# PulseGenerator.net
KiCad netlist of a schematic drawn in EAGLE
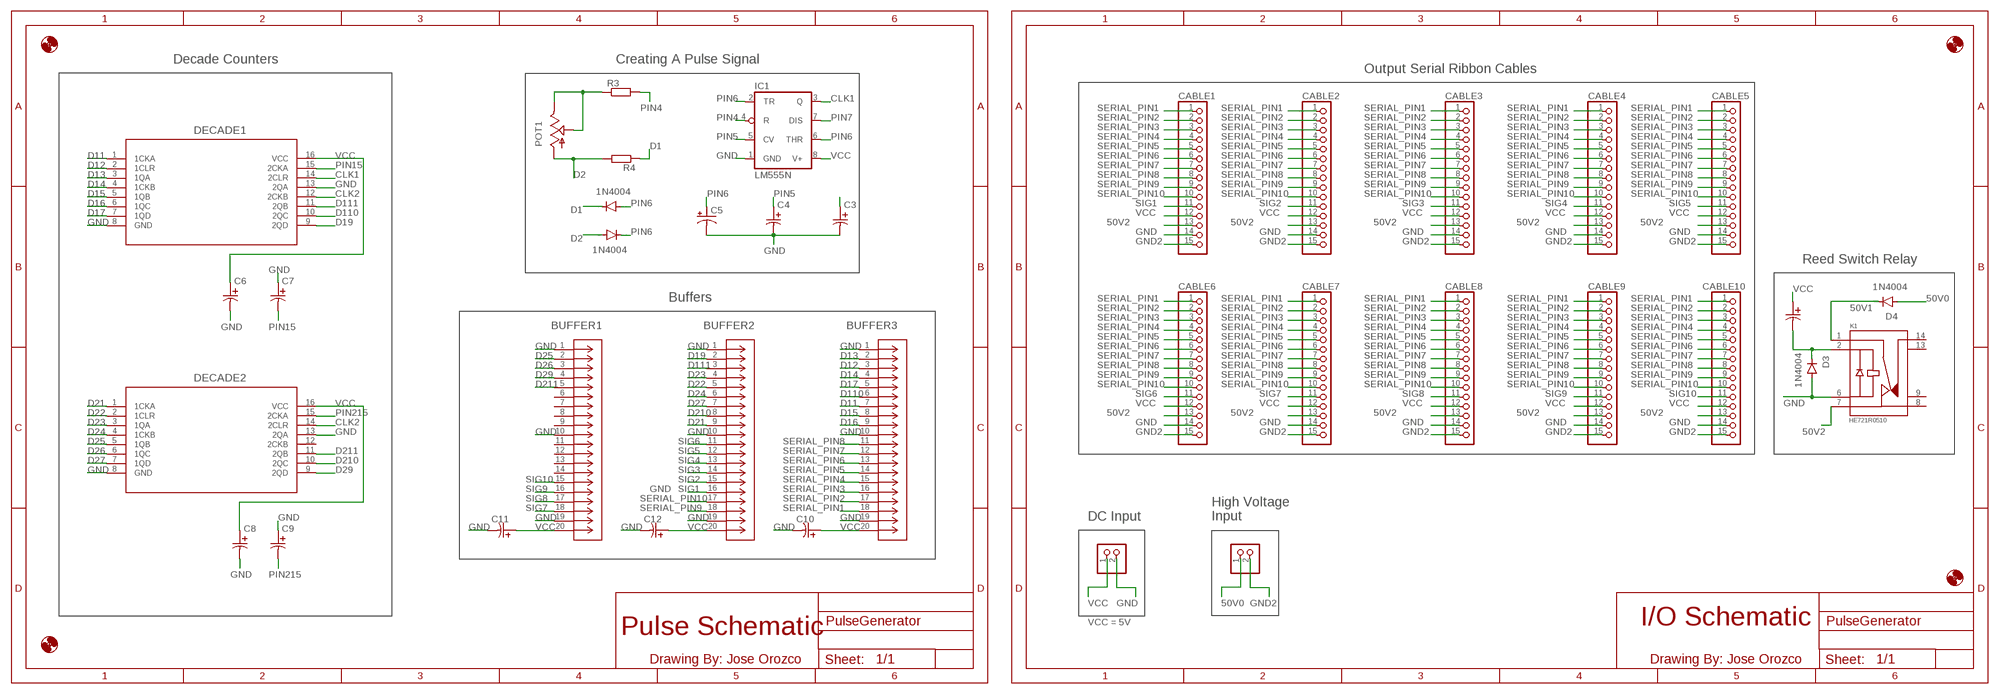
[diagram p0: schematic, sheet 1]

(export (version "E")
  (design (tool "Eeschema 10.0.6"))
  (components
    (comp (ref "BUFFER1")
      (value "4820-3000-CP")
      (footprint "eagle-import:CONN_3000_3MM")
      (fields (field (name "COPYRIGHT") "Copyright (C) 2018 Accelerated Designs. All rights reserved"))
      (libsource (lib "eagle-import") (part "4820-3000-CP"))
    )
    (comp (ref "BUFFER2")
      (value "4820-3000-CP")
      (footprint "eagle-import:CONN_3000_3MM")
      (fields (field (name "COPYRIGHT") "Copyright (C) 2018 Accelerated Designs. All rights reserved"))
      (libsource (lib "eagle-import") (part "4820-3000-CP"))
    )
    (comp (ref "BUFFER3")
      (value "4820-3000-CP")
      (footprint "eagle-import:CONN_3000_3MM")
      (fields (field (name "COPYRIGHT") "Copyright (C) 2018 Accelerated Designs. All rights reserved"))
      (libsource (lib "eagle-import") (part "4820-3000-CP"))
    )
    (comp (ref "C1")
      (value "C322C104K5R5TA")
      (footprint "eagle-import:CAP_C322_KEM")
      (libsource (lib "eagle-import") (part "C322C104K5R5TA"))
    )
    (comp (ref "C3")
      (value "C322C104K5R5TA")
      (footprint "eagle-import:CAP_C322_KEM")
      (libsource (lib "eagle-import") (part "C322C104K5R5TA"))
    )
    (comp (ref "C4")
      (value "C322C104K5R5TA")
      (footprint "eagle-import:CAP_C322_KEM")
      (libsource (lib "eagle-import") (part "C322C104K5R5TA"))
    )
    (comp (ref "C5")
      (value "CPOL-USTAP5-45")
      (footprint "eagle-import:TAP5-45")
      (libsource (lib "eagle-import") (part "CPOL-USTAP5-45"))
    )
    (comp (ref "C6")
      (value "C322C104K5R5TA")
      (footprint "eagle-import:CAP_C322_KEM")
      (libsource (lib "eagle-import") (part "C322C104K5R5TA"))
    )
    (comp (ref "C7")
      (value "C322C104K5R5TA")
      (footprint "eagle-import:CAP_C322_KEM")
      (libsource (lib "eagle-import") (part "C322C104K5R5TA"))
    )
    (comp (ref "C8")
      (value "C322C104K5R5TA")
      (footprint "eagle-import:CAP_C322_KEM")
      (libsource (lib "eagle-import") (part "C322C104K5R5TA"))
    )
    (comp (ref "C9")
      (value "C322C104K5R5TA")
      (footprint "eagle-import:CAP_C322_KEM")
      (libsource (lib "eagle-import") (part "C322C104K5R5TA"))
    )
    (comp (ref "C10")
      (value "C322C104K5R5TA")
      (footprint "eagle-import:CAP_C322_KEM")
      (libsource (lib "eagle-import") (part "C322C104K5R5TA"))
    )
    (comp (ref "C11")
      (value "C322C104K5R5TA")
      (footprint "eagle-import:CAP_C322_KEM")
      (libsource (lib "eagle-import") (part "C322C104K5R5TA"))
    )
    (comp (ref "C12")
      (value "C322C104K5R5TA")
      (footprint "eagle-import:CAP_C322_KEM")
      (libsource (lib "eagle-import") (part "C322C104K5R5TA"))
    )
    (comp (ref "CABLE1")
      (value "PINHD-1X15")
      (footprint "eagle-import:1X15")
      (libsource (lib "eagle-import") (part "PINHD-1X15"))
    )
    (comp (ref "CABLE2")
      (value "PINHD-1X15")
      (footprint "eagle-import:1X15")
      (libsource (lib "eagle-import") (part "PINHD-1X15"))
    )
    (comp (ref "CABLE3")
      (value "PINHD-1X15")
      (footprint "eagle-import:1X15")
      (libsource (lib "eagle-import") (part "PINHD-1X15"))
    )
    (comp (ref "CABLE4")
      (value "PINHD-1X15")
      (footprint "eagle-import:1X15")
      (libsource (lib "eagle-import") (part "PINHD-1X15"))
    )
    (comp (ref "CABLE5")
      (value "PINHD-1X15")
      (footprint "eagle-import:1X15")
      (libsource (lib "eagle-import") (part "PINHD-1X15"))
    )
    (comp (ref "CABLE6")
      (value "PINHD-1X15")
      (footprint "eagle-import:1X15")
      (libsource (lib "eagle-import") (part "PINHD-1X15"))
    )
    (comp (ref "CABLE7")
      (value "PINHD-1X15")
      (footprint "eagle-import:1X15")
      (libsource (lib "eagle-import") (part "PINHD-1X15"))
    )
    (comp (ref "CABLE8")
      (value "PINHD-1X15")
      (footprint "eagle-import:1X15")
      (libsource (lib "eagle-import") (part "PINHD-1X15"))
    )
    (comp (ref "CABLE9")
      (value "PINHD-1X15")
      (footprint "eagle-import:1X15")
      (libsource (lib "eagle-import") (part "PINHD-1X15"))
    )
    (comp (ref "CABLE10")
      (value "PINHD-1X15")
      (footprint "eagle-import:1X15")
      (libsource (lib "eagle-import") (part "PINHD-1X15"))
    )
    (comp (ref "D1")
      (value "1N4004")
      (footprint "eagle-import:DO41-10")
      (libsource (lib "eagle-import") (part "1N4004"))
    )
    (comp (ref "D2")
      (value "1N4004")
      (footprint "eagle-import:DO41-10")
      (libsource (lib "eagle-import") (part "1N4004"))
    )
    (comp (ref "D3")
      (value "1N4004")
      (footprint "eagle-import:DO41-10")
      (libsource (lib "eagle-import") (part "1N4004"))
    )
    (comp (ref "D4")
      (value "1N4004")
      (footprint "eagle-import:DO41-10")
      (libsource (lib "eagle-import") (part "1N4004"))
    )
    (comp (ref "DECADE1")
      (value "SN74LS390N")
      (footprint "eagle-import:N16")
      (fields
        (field (name "GENERIC_PART_NUMBER") "SN74LS390")
        (field (name "MANUFACTURER") "Texas Instruments")
      )
      (libsource (lib "eagle-import") (part "SN74LS390N"))
    )
    (comp (ref "DECADE2")
      (value "SN74LS390N")
      (footprint "eagle-import:N16")
      (fields
        (field (name "GENERIC_PART_NUMBER") "SN74LS390")
        (field (name "MANUFACTURER") "Texas Instruments")
      )
      (libsource (lib "eagle-import") (part "SN74LS390N"))
    )
    (comp (ref "H1")
      (value "MOUNT-HOLE2.8")
      (footprint "eagle-import:2,8")
      (libsource (lib "eagle-import") (part "MOUNT-HOLE2.8"))
    )
    (comp (ref "H2")
      (value "MOUNT-HOLE2.8")
      (footprint "eagle-import:2,8")
      (libsource (lib "eagle-import") (part "MOUNT-HOLE2.8"))
    )
    (comp (ref "H3")
      (value "MOUNT-HOLE2.8")
      (footprint "eagle-import:2,8")
      (libsource (lib "eagle-import") (part "MOUNT-HOLE2.8"))
    )
    (comp (ref "H4")
      (value "MOUNT-HOLE2.8")
      (footprint "eagle-import:2,8")
      (libsource (lib "eagle-import") (part "MOUNT-HOLE2.8"))
    )
    (comp (ref "IC1")
      (value "LM555N")
      (footprint "eagle-import:DIL08")
      (libsource (lib "eagle-import") (part "555NLM"))
    )
    (comp (ref "JP1")
      (value "PINHD-1X2")
      (footprint "eagle-import:1X02")
      (libsource (lib "eagle-import") (part "PINHD-1X2"))
    )
    (comp (ref "JP2")
      (value "PINHD-1X2")
      (footprint "eagle-import:1X02")
      (libsource (lib "eagle-import") (part "PINHD-1X2"))
    )
    (comp (ref "K1")
      (value "HE721R0510")
      (footprint "eagle-import:RELAY_HE721R0510")
      (fields (field (name "DIGI-KEY_PART_NUMBER") "F11467-ND") (field (name "MF") "Littelfuse Inc."))
      (libsource (lib "eagle-import") (part "HE721R0510"))
    )
    (comp (ref "POT1")
      (value "TRIM_US-S63X")
      (footprint "eagle-import:S63X")
      (libsource (lib "eagle-import") (part "TRIM_US-S63X"))
    )
    (comp (ref "R3")
      (value "R-EU_0309/10")
      (footprint "eagle-import:0309_10")
      (libsource (lib "eagle-import") (part "R-EU_0309/10"))
    )
    (comp (ref "R4")
      (value "R-EU_0309/10")
      (footprint "eagle-import:0309_10")
      (libsource (lib "eagle-import") (part "R-EU_0309/10"))
    )
  )
  (nets
    (net (code "1") (name "/50V0") (class "Default")
      (node (ref "D4") (pin "A") (pinfunction "A_A") (pintype "passive"))
      (node (ref "JP2") (pin "1") (pinfunction "1_1") (pintype "passive"))
    )
    (net (code "2") (name "/50V1") (class "Default")
      (node (ref "D4") (pin "C") (pinfunction "C_C") (pintype "passive"))
      (node (ref "K1") (pin "1") (pinfunction "1_1") (pintype "passive"))
    )
    (net (code "3") (name "/50V2") (class "Default")
      (node (ref "CABLE1") (pin "13") (pinfunction "13_13") (pintype "passive"))
      (node (ref "CABLE10") (pin "13") (pinfunction "13_13") (pintype "passive"))
      (node (ref "CABLE2") (pin "13") (pinfunction "13_13") (pintype "passive"))
      (node (ref "CABLE3") (pin "13") (pinfunction "13_13") (pintype "passive"))
      (node (ref "CABLE4") (pin "13") (pinfunction "13_13") (pintype "passive"))
      (node (ref "CABLE5") (pin "13") (pinfunction "13_13") (pintype "passive"))
      (node (ref "CABLE6") (pin "13") (pinfunction "13_13") (pintype "passive"))
      (node (ref "CABLE7") (pin "13") (pinfunction "13_13") (pintype "passive"))
      (node (ref "CABLE8") (pin "13") (pinfunction "13_13") (pintype "passive"))
      (node (ref "CABLE9") (pin "13") (pinfunction "13_13") (pintype "passive"))
      (node (ref "K1") (pin "7") (pinfunction "7_7") (pintype "passive"))
    )
    (net (code "4") (name "/CLK1") (class "Default")
      (node (ref "DECADE1") (pin "14") (pinfunction "2CLR_14") (pintype "input"))
      (node (ref "IC1") (pin "3") (pinfunction "Q_3") (pintype "output"))
    )
    (net (code "5") (name "/CLK2") (class "Default")
      (node (ref "DECADE1") (pin "12") (pinfunction "2CKB_12") (pintype "input"))
      (node (ref "DECADE2") (pin "14") (pinfunction "2CLR_14") (pintype "input"))
    )
    (net (code "6") (name "/D1") (class "Default")
      (node (ref "D1") (pin "C") (pinfunction "C_C") (pintype "passive"))
      (node (ref "R4") (pin "1") (pinfunction "1_1") (pintype "passive"))
    )
    (net (code "7") (name "/D2") (class "Default")
      (node (ref "D2") (pin "A") (pinfunction "A_A") (pintype "passive"))
      (node (ref "POT1") (pin "A") (pinfunction "A_A") (pintype "passive"))
      (node (ref "R4") (pin "2") (pinfunction "2_2") (pintype "passive"))
    )
    (net (code "8") (name "/D11") (class "Default")
      (node (ref "BUFFER3") (pin "7") (pinfunction "7_7") (pintype "passive"))
      (node (ref "DECADE1") (pin "1") (pinfunction "1CKA_1") (pintype "input"))
    )
    (net (code "9") (name "/D12") (class "Default")
      (node (ref "BUFFER3") (pin "3") (pinfunction "3_3") (pintype "passive"))
      (node (ref "DECADE1") (pin "2") (pinfunction "1CLR_2") (pintype "input"))
    )
    (net (code "10") (name "/D13") (class "Default")
      (node (ref "BUFFER3") (pin "2") (pinfunction "2_2") (pintype "passive"))
      (node (ref "DECADE1") (pin "3") (pinfunction "1QA_3") (pintype "output"))
    )
    (net (code "11") (name "/D14") (class "Default")
      (node (ref "BUFFER3") (pin "4") (pinfunction "4_4") (pintype "passive"))
      (node (ref "DECADE1") (pin "4") (pinfunction "1CKB_4") (pintype "input"))
    )
    (net (code "12") (name "/D15") (class "Default")
      (node (ref "BUFFER3") (pin "8") (pinfunction "8_8") (pintype "passive"))
      (node (ref "DECADE1") (pin "5") (pinfunction "1QB_5") (pintype "output"))
    )
    (net (code "13") (name "/D16") (class "Default")
      (node (ref "BUFFER3") (pin "9") (pinfunction "9_9") (pintype "passive"))
      (node (ref "DECADE1") (pin "6") (pinfunction "1QC_6") (pintype "output"))
    )
    (net (code "14") (name "/D17") (class "Default")
      (node (ref "BUFFER3") (pin "5") (pinfunction "5_5") (pintype "passive"))
      (node (ref "DECADE1") (pin "7") (pinfunction "1QD_7") (pintype "output"))
    )
    (net (code "15") (name "/D19") (class "Default")
      (node (ref "BUFFER2") (pin "2") (pinfunction "2_2") (pintype "passive"))
      (node (ref "DECADE1") (pin "9") (pinfunction "2QD_9") (pintype "output"))
    )
    (net (code "16") (name "/D21") (class "Default")
      (node (ref "BUFFER2") (pin "9") (pinfunction "9_9") (pintype "passive"))
      (node (ref "DECADE2") (pin "1") (pinfunction "1CKA_1") (pintype "input"))
    )
    (net (code "17") (name "/D22") (class "Default")
      (node (ref "BUFFER2") (pin "5") (pinfunction "5_5") (pintype "passive"))
      (node (ref "DECADE2") (pin "2") (pinfunction "1CLR_2") (pintype "input"))
    )
    (net (code "18") (name "/D23") (class "Default")
      (node (ref "BUFFER2") (pin "4") (pinfunction "4_4") (pintype "passive"))
      (node (ref "DECADE2") (pin "3") (pinfunction "1QA_3") (pintype "output"))
    )
    (net (code "19") (name "/D24") (class "Default")
      (node (ref "BUFFER2") (pin "6") (pinfunction "6_6") (pintype "passive"))
      (node (ref "DECADE2") (pin "4") (pinfunction "1CKB_4") (pintype "input"))
    )
    (net (code "20") (name "/D25") (class "Default")
      (node (ref "BUFFER1") (pin "2") (pinfunction "2_2") (pintype "passive"))
      (node (ref "DECADE2") (pin "5") (pinfunction "1QB_5") (pintype "output"))
    )
    (net (code "21") (name "/D26") (class "Default")
      (node (ref "BUFFER1") (pin "3") (pinfunction "3_3") (pintype "passive"))
      (node (ref "DECADE2") (pin "6") (pinfunction "1QC_6") (pintype "output"))
    )
    (net (code "22") (name "/D27") (class "Default")
      (node (ref "BUFFER2") (pin "7") (pinfunction "7_7") (pintype "passive"))
      (node (ref "DECADE2") (pin "7") (pinfunction "1QD_7") (pintype "output"))
    )
    (net (code "23") (name "/D29") (class "Default")
      (node (ref "BUFFER1") (pin "4") (pinfunction "4_4") (pintype "passive"))
      (node (ref "DECADE2") (pin "9") (pinfunction "2QD_9") (pintype "output"))
    )
    (net (code "24") (name "/D110") (class "Default")
      (node (ref "BUFFER3") (pin "6") (pinfunction "6_6") (pintype "passive"))
      (node (ref "DECADE1") (pin "10") (pinfunction "2QC_10") (pintype "output"))
    )
    (net (code "25") (name "/D111") (class "Default")
      (node (ref "BUFFER2") (pin "3") (pinfunction "3_3") (pintype "passive"))
      (node (ref "DECADE1") (pin "11") (pinfunction "2QB_11") (pintype "output"))
    )
    (net (code "26") (name "/D210") (class "Default")
      (node (ref "BUFFER2") (pin "8") (pinfunction "8_8") (pintype "passive"))
      (node (ref "DECADE2") (pin "10") (pinfunction "2QC_10") (pintype "output"))
    )
    (net (code "27") (name "/D211") (class "Default")
      (node (ref "BUFFER1") (pin "5") (pinfunction "5_5") (pintype "passive"))
      (node (ref "DECADE2") (pin "11") (pinfunction "2QB_11") (pintype "output"))
    )
    (net (code "28") (name "/GND") (class "Default")
      (node (ref "BUFFER1") (pin "1") (pinfunction "1_1") (pintype "passive"))
      (node (ref "BUFFER1") (pin "10") (pinfunction "10_10") (pintype "passive"))
      (node (ref "BUFFER1") (pin "19") (pinfunction "19_19") (pintype "passive"))
      (node (ref "BUFFER2") (pin "1") (pinfunction "1_1") (pintype "passive"))
      (node (ref "BUFFER2") (pin "10") (pinfunction "10_10") (pintype "passive"))
      (node (ref "BUFFER2") (pin "19") (pinfunction "19_19") (pintype "passive"))
      (node (ref "BUFFER3") (pin "1") (pinfunction "1_1") (pintype "passive"))
      (node (ref "BUFFER3") (pin "10") (pinfunction "10_10") (pintype "passive"))
      (node (ref "BUFFER3") (pin "19") (pinfunction "19_19") (pintype "passive"))
      (node (ref "C10") (pin "2") (pinfunction "2_2") (pintype "passive"))
      (node (ref "C11") (pin "2") (pinfunction "2_2") (pintype "passive"))
      (node (ref "C12") (pin "2") (pinfunction "2_2") (pintype "passive"))
      (node (ref "C3") (pin "2") (pinfunction "2_2") (pintype "passive"))
      (node (ref "C4") (pin "2") (pinfunction "2_2") (pintype "passive"))
      (node (ref "C5") (pin "-") (pinfunction "-_-") (pintype "passive"))
      (node (ref "C6") (pin "2") (pinfunction "2_2") (pintype "passive"))
      (node (ref "C7") (pin "1") (pinfunction "1_1") (pintype "passive"))
      (node (ref "C8") (pin "2") (pinfunction "2_2") (pintype "passive"))
      (node (ref "C9") (pin "1") (pinfunction "1_1") (pintype "passive"))
      (node (ref "CABLE1") (pin "14") (pinfunction "14_14") (pintype "passive"))
      (node (ref "CABLE10") (pin "14") (pinfunction "14_14") (pintype "passive"))
      (node (ref "CABLE2") (pin "14") (pinfunction "14_14") (pintype "passive"))
      (node (ref "CABLE3") (pin "14") (pinfunction "14_14") (pintype "passive"))
      (node (ref "CABLE4") (pin "14") (pinfunction "14_14") (pintype "passive"))
      (node (ref "CABLE5") (pin "14") (pinfunction "14_14") (pintype "passive"))
      (node (ref "CABLE6") (pin "14") (pinfunction "14_14") (pintype "passive"))
      (node (ref "CABLE7") (pin "14") (pinfunction "14_14") (pintype "passive"))
      (node (ref "CABLE8") (pin "14") (pinfunction "14_14") (pintype "passive"))
      (node (ref "CABLE9") (pin "14") (pinfunction "14_14") (pintype "passive"))
      (node (ref "D3") (pin "A") (pinfunction "A_A") (pintype "passive"))
      (node (ref "DECADE1") (pin "13") (pinfunction "2QA_13") (pintype "output"))
      (node (ref "DECADE1") (pin "8") (pinfunction "GND_8") (pintype "power_in"))
      (node (ref "DECADE2") (pin "13") (pinfunction "2QA_13") (pintype "output"))
      (node (ref "DECADE2") (pin "8") (pinfunction "GND_8") (pintype "power_in"))
      (node (ref "IC1") (pin "1") (pinfunction "GND_1") (pintype "power_in"))
      (node (ref "JP1") (pin "2") (pinfunction "2_2") (pintype "passive"))
      (node (ref "K1") (pin "6") (pinfunction "6_6") (pintype "passive"))
    )
    (net (code "29") (name "/GND2") (class "Default")
      (node (ref "CABLE1") (pin "15") (pinfunction "15_15") (pintype "passive"))
      (node (ref "CABLE10") (pin "15") (pinfunction "15_15") (pintype "passive"))
      (node (ref "CABLE2") (pin "15") (pinfunction "15_15") (pintype "passive"))
      (node (ref "CABLE3") (pin "15") (pinfunction "15_15") (pintype "passive"))
      (node (ref "CABLE4") (pin "15") (pinfunction "15_15") (pintype "passive"))
      (node (ref "CABLE5") (pin "15") (pinfunction "15_15") (pintype "passive"))
      (node (ref "CABLE6") (pin "15") (pinfunction "15_15") (pintype "passive"))
      (node (ref "CABLE7") (pin "15") (pinfunction "15_15") (pintype "passive"))
      (node (ref "CABLE8") (pin "15") (pinfunction "15_15") (pintype "passive"))
      (node (ref "CABLE9") (pin "15") (pinfunction "15_15") (pintype "passive"))
      (node (ref "JP2") (pin "2") (pinfunction "2_2") (pintype "passive"))
    )
    (net (code "30") (name "/PIN4") (class "Default")
      (node (ref "IC1") (pin "4") (pinfunction "R_4") (pintype "input"))
      (node (ref "R3") (pin "2") (pinfunction "2_2") (pintype "passive"))
    )
    (net (code "31") (name "/PIN5") (class "Default")
      (node (ref "C4") (pin "1") (pinfunction "1_1") (pintype "passive"))
      (node (ref "IC1") (pin "5") (pinfunction "CV_5") (pintype "input"))
    )
    (net (code "32") (name "/PIN6") (class "Default")
      (node (ref "C5") (pin "+") (pinfunction "+_+") (pintype "passive"))
      (node (ref "D1") (pin "A") (pinfunction "A_A") (pintype "passive"))
      (node (ref "D2") (pin "C") (pinfunction "C_C") (pintype "passive"))
      (node (ref "IC1") (pin "2") (pinfunction "TR_2") (pintype "input"))
      (node (ref "IC1") (pin "6") (pinfunction "THR_6") (pintype "input"))
    )
    (net (code "33") (name "/PIN7") (class "Default")
      (node (ref "IC1") (pin "7") (pinfunction "DIS_7") (pintype "input"))
    )
    (net (code "34") (name "/PIN15") (class "Default")
      (node (ref "C7") (pin "2") (pinfunction "2_2") (pintype "passive"))
      (node (ref "DECADE1") (pin "15") (pinfunction "2CKA_15") (pintype "input"))
    )
    (net (code "35") (name "/PIN215") (class "Default")
      (node (ref "C9") (pin "2") (pinfunction "2_2") (pintype "passive"))
      (node (ref "DECADE2") (pin "15") (pinfunction "2CKA_15") (pintype "input"))
    )
    (net (code "36") (name "/SERIAL_PIN1") (class "Default")
      (node (ref "BUFFER3") (pin "18") (pinfunction "18_18") (pintype "passive"))
      (node (ref "CABLE1") (pin "1") (pinfunction "1_1") (pintype "passive"))
      (node (ref "CABLE10") (pin "1") (pinfunction "1_1") (pintype "passive"))
      (node (ref "CABLE2") (pin "1") (pinfunction "1_1") (pintype "passive"))
      (node (ref "CABLE3") (pin "1") (pinfunction "1_1") (pintype "passive"))
      (node (ref "CABLE4") (pin "1") (pinfunction "1_1") (pintype "passive"))
      (node (ref "CABLE5") (pin "1") (pinfunction "1_1") (pintype "passive"))
      (node (ref "CABLE6") (pin "1") (pinfunction "1_1") (pintype "passive"))
      (node (ref "CABLE7") (pin "1") (pinfunction "1_1") (pintype "passive"))
      (node (ref "CABLE8") (pin "1") (pinfunction "1_1") (pintype "passive"))
      (node (ref "CABLE9") (pin "1") (pinfunction "1_1") (pintype "passive"))
    )
    (net (code "37") (name "/SERIAL_PIN2") (class "Default")
      (node (ref "BUFFER3") (pin "17") (pinfunction "17_17") (pintype "passive"))
      (node (ref "CABLE1") (pin "2") (pinfunction "2_2") (pintype "passive"))
      (node (ref "CABLE10") (pin "2") (pinfunction "2_2") (pintype "passive"))
      (node (ref "CABLE2") (pin "2") (pinfunction "2_2") (pintype "passive"))
      (node (ref "CABLE3") (pin "2") (pinfunction "2_2") (pintype "passive"))
      (node (ref "CABLE4") (pin "2") (pinfunction "2_2") (pintype "passive"))
      (node (ref "CABLE5") (pin "2") (pinfunction "2_2") (pintype "passive"))
      (node (ref "CABLE6") (pin "2") (pinfunction "2_2") (pintype "passive"))
      (node (ref "CABLE7") (pin "2") (pinfunction "2_2") (pintype "passive"))
      (node (ref "CABLE8") (pin "2") (pinfunction "2_2") (pintype "passive"))
      (node (ref "CABLE9") (pin "2") (pinfunction "2_2") (pintype "passive"))
    )
    (net (code "38") (name "/SERIAL_PIN3") (class "Default")
      (node (ref "BUFFER3") (pin "16") (pinfunction "16_16") (pintype "passive"))
      (node (ref "CABLE1") (pin "3") (pinfunction "3_3") (pintype "passive"))
      (node (ref "CABLE10") (pin "3") (pinfunction "3_3") (pintype "passive"))
      (node (ref "CABLE2") (pin "3") (pinfunction "3_3") (pintype "passive"))
      (node (ref "CABLE3") (pin "3") (pinfunction "3_3") (pintype "passive"))
      (node (ref "CABLE4") (pin "3") (pinfunction "3_3") (pintype "passive"))
      (node (ref "CABLE5") (pin "3") (pinfunction "3_3") (pintype "passive"))
      (node (ref "CABLE6") (pin "3") (pinfunction "3_3") (pintype "passive"))
      (node (ref "CABLE7") (pin "3") (pinfunction "3_3") (pintype "passive"))
      (node (ref "CABLE8") (pin "3") (pinfunction "3_3") (pintype "passive"))
      (node (ref "CABLE9") (pin "3") (pinfunction "3_3") (pintype "passive"))
    )
    (net (code "39") (name "/SERIAL_PIN4") (class "Default")
      (node (ref "BUFFER3") (pin "15") (pinfunction "15_15") (pintype "passive"))
      (node (ref "CABLE1") (pin "4") (pinfunction "4_4") (pintype "passive"))
      (node (ref "CABLE10") (pin "4") (pinfunction "4_4") (pintype "passive"))
      (node (ref "CABLE2") (pin "4") (pinfunction "4_4") (pintype "passive"))
      (node (ref "CABLE3") (pin "4") (pinfunction "4_4") (pintype "passive"))
      (node (ref "CABLE4") (pin "4") (pinfunction "4_4") (pintype "passive"))
      (node (ref "CABLE5") (pin "4") (pinfunction "4_4") (pintype "passive"))
      (node (ref "CABLE6") (pin "4") (pinfunction "4_4") (pintype "passive"))
      (node (ref "CABLE7") (pin "4") (pinfunction "4_4") (pintype "passive"))
      (node (ref "CABLE8") (pin "4") (pinfunction "4_4") (pintype "passive"))
      (node (ref "CABLE9") (pin "4") (pinfunction "4_4") (pintype "passive"))
    )
    (net (code "40") (name "/SERIAL_PIN5") (class "Default")
      (node (ref "BUFFER3") (pin "14") (pinfunction "14_14") (pintype "passive"))
      (node (ref "CABLE1") (pin "5") (pinfunction "5_5") (pintype "passive"))
      (node (ref "CABLE10") (pin "5") (pinfunction "5_5") (pintype "passive"))
      (node (ref "CABLE2") (pin "5") (pinfunction "5_5") (pintype "passive"))
      (node (ref "CABLE3") (pin "5") (pinfunction "5_5") (pintype "passive"))
      (node (ref "CABLE4") (pin "5") (pinfunction "5_5") (pintype "passive"))
      (node (ref "CABLE5") (pin "5") (pinfunction "5_5") (pintype "passive"))
      (node (ref "CABLE6") (pin "5") (pinfunction "5_5") (pintype "passive"))
      (node (ref "CABLE7") (pin "5") (pinfunction "5_5") (pintype "passive"))
      (node (ref "CABLE8") (pin "5") (pinfunction "5_5") (pintype "passive"))
      (node (ref "CABLE9") (pin "5") (pinfunction "5_5") (pintype "passive"))
    )
    (net (code "41") (name "/SERIAL_PIN6") (class "Default")
      (node (ref "BUFFER3") (pin "13") (pinfunction "13_13") (pintype "passive"))
      (node (ref "CABLE1") (pin "6") (pinfunction "6_6") (pintype "passive"))
      (node (ref "CABLE10") (pin "6") (pinfunction "6_6") (pintype "passive"))
      (node (ref "CABLE2") (pin "6") (pinfunction "6_6") (pintype "passive"))
      (node (ref "CABLE3") (pin "6") (pinfunction "6_6") (pintype "passive"))
      (node (ref "CABLE4") (pin "6") (pinfunction "6_6") (pintype "passive"))
      (node (ref "CABLE5") (pin "6") (pinfunction "6_6") (pintype "passive"))
      (node (ref "CABLE6") (pin "6") (pinfunction "6_6") (pintype "passive"))
      (node (ref "CABLE7") (pin "6") (pinfunction "6_6") (pintype "passive"))
      (node (ref "CABLE8") (pin "6") (pinfunction "6_6") (pintype "passive"))
      (node (ref "CABLE9") (pin "6") (pinfunction "6_6") (pintype "passive"))
    )
    (net (code "42") (name "/SERIAL_PIN7") (class "Default")
      (node (ref "BUFFER3") (pin "12") (pinfunction "12_12") (pintype "passive"))
      (node (ref "CABLE1") (pin "7") (pinfunction "7_7") (pintype "passive"))
      (node (ref "CABLE10") (pin "7") (pinfunction "7_7") (pintype "passive"))
      (node (ref "CABLE2") (pin "7") (pinfunction "7_7") (pintype "passive"))
      (node (ref "CABLE3") (pin "7") (pinfunction "7_7") (pintype "passive"))
      (node (ref "CABLE4") (pin "7") (pinfunction "7_7") (pintype "passive"))
      (node (ref "CABLE5") (pin "7") (pinfunction "7_7") (pintype "passive"))
      (node (ref "CABLE6") (pin "7") (pinfunction "7_7") (pintype "passive"))
      (node (ref "CABLE7") (pin "7") (pinfunction "7_7") (pintype "passive"))
      (node (ref "CABLE8") (pin "7") (pinfunction "7_7") (pintype "passive"))
      (node (ref "CABLE9") (pin "7") (pinfunction "7_7") (pintype "passive"))
    )
    (net (code "43") (name "/SERIAL_PIN8") (class "Default")
      (node (ref "BUFFER3") (pin "11") (pinfunction "11_11") (pintype "passive"))
      (node (ref "CABLE1") (pin "8") (pinfunction "8_8") (pintype "passive"))
      (node (ref "CABLE10") (pin "8") (pinfunction "8_8") (pintype "passive"))
      (node (ref "CABLE2") (pin "8") (pinfunction "8_8") (pintype "passive"))
      (node (ref "CABLE3") (pin "8") (pinfunction "8_8") (pintype "passive"))
      (node (ref "CABLE4") (pin "8") (pinfunction "8_8") (pintype "passive"))
      (node (ref "CABLE5") (pin "8") (pinfunction "8_8") (pintype "passive"))
      (node (ref "CABLE6") (pin "8") (pinfunction "8_8") (pintype "passive"))
      (node (ref "CABLE7") (pin "8") (pinfunction "8_8") (pintype "passive"))
      (node (ref "CABLE8") (pin "8") (pinfunction "8_8") (pintype "passive"))
      (node (ref "CABLE9") (pin "8") (pinfunction "8_8") (pintype "passive"))
    )
    (net (code "44") (name "/SERIAL_PIN9") (class "Default")
      (node (ref "BUFFER2") (pin "18") (pinfunction "18_18") (pintype "passive"))
      (node (ref "CABLE1") (pin "9") (pinfunction "9_9") (pintype "passive"))
      (node (ref "CABLE10") (pin "9") (pinfunction "9_9") (pintype "passive"))
      (node (ref "CABLE2") (pin "9") (pinfunction "9_9") (pintype "passive"))
      (node (ref "CABLE3") (pin "9") (pinfunction "9_9") (pintype "passive"))
      (node (ref "CABLE4") (pin "9") (pinfunction "9_9") (pintype "passive"))
      (node (ref "CABLE5") (pin "9") (pinfunction "9_9") (pintype "passive"))
      (node (ref "CABLE6") (pin "9") (pinfunction "9_9") (pintype "passive"))
      (node (ref "CABLE7") (pin "9") (pinfunction "9_9") (pintype "passive"))
      (node (ref "CABLE8") (pin "9") (pinfunction "9_9") (pintype "passive"))
      (node (ref "CABLE9") (pin "9") (pinfunction "9_9") (pintype "passive"))
    )
    (net (code "45") (name "/SERIAL_PIN10") (class "Default")
      (node (ref "BUFFER2") (pin "17") (pinfunction "17_17") (pintype "passive"))
      (node (ref "CABLE1") (pin "10") (pinfunction "10_10") (pintype "passive"))
      (node (ref "CABLE10") (pin "10") (pinfunction "10_10") (pintype "passive"))
      (node (ref "CABLE2") (pin "10") (pinfunction "10_10") (pintype "passive"))
      (node (ref "CABLE3") (pin "10") (pinfunction "10_10") (pintype "passive"))
      (node (ref "CABLE4") (pin "10") (pinfunction "10_10") (pintype "passive"))
      (node (ref "CABLE5") (pin "10") (pinfunction "10_10") (pintype "passive"))
      (node (ref "CABLE6") (pin "10") (pinfunction "10_10") (pintype "passive"))
      (node (ref "CABLE7") (pin "10") (pinfunction "10_10") (pintype "passive"))
      (node (ref "CABLE8") (pin "10") (pinfunction "10_10") (pintype "passive"))
      (node (ref "CABLE9") (pin "10") (pinfunction "10_10") (pintype "passive"))
    )
    (net (code "46") (name "/SIG1") (class "Default")
      (node (ref "BUFFER2") (pin "16") (pinfunction "16_16") (pintype "passive"))
      (node (ref "CABLE1") (pin "11") (pinfunction "11_11") (pintype "passive"))
    )
    (net (code "47") (name "/SIG2") (class "Default")
      (node (ref "BUFFER2") (pin "15") (pinfunction "15_15") (pintype "passive"))
      (node (ref "CABLE2") (pin "11") (pinfunction "11_11") (pintype "passive"))
    )
    (net (code "48") (name "/SIG3") (class "Default")
      (node (ref "BUFFER2") (pin "14") (pinfunction "14_14") (pintype "passive"))
      (node (ref "CABLE3") (pin "11") (pinfunction "11_11") (pintype "passive"))
    )
    (net (code "49") (name "/SIG4") (class "Default")
      (node (ref "BUFFER2") (pin "13") (pinfunction "13_13") (pintype "passive"))
      (node (ref "CABLE4") (pin "11") (pinfunction "11_11") (pintype "passive"))
    )
    (net (code "50") (name "/SIG5") (class "Default")
      (node (ref "BUFFER2") (pin "12") (pinfunction "12_12") (pintype "passive"))
      (node (ref "CABLE5") (pin "11") (pinfunction "11_11") (pintype "passive"))
    )
    (net (code "51") (name "/SIG6") (class "Default")
      (node (ref "BUFFER2") (pin "11") (pinfunction "11_11") (pintype "passive"))
      (node (ref "CABLE6") (pin "11") (pinfunction "11_11") (pintype "passive"))
    )
    (net (code "52") (name "/SIG7") (class "Default")
      (node (ref "BUFFER1") (pin "18") (pinfunction "18_18") (pintype "passive"))
      (node (ref "CABLE7") (pin "11") (pinfunction "11_11") (pintype "passive"))
    )
    (net (code "53") (name "/SIG8") (class "Default")
      (node (ref "BUFFER1") (pin "17") (pinfunction "17_17") (pintype "passive"))
      (node (ref "CABLE8") (pin "11") (pinfunction "11_11") (pintype "passive"))
    )
    (net (code "54") (name "/SIG9") (class "Default")
      (node (ref "BUFFER1") (pin "16") (pinfunction "16_16") (pintype "passive"))
      (node (ref "CABLE9") (pin "11") (pinfunction "11_11") (pintype "passive"))
    )
    (net (code "55") (name "/SIG10") (class "Default")
      (node (ref "BUFFER1") (pin "15") (pinfunction "15_15") (pintype "passive"))
      (node (ref "CABLE10") (pin "11") (pinfunction "11_11") (pintype "passive"))
    )
    (net (code "56") (name "/VCC") (class "Default")
      (node (ref "BUFFER1") (pin "20") (pinfunction "20_20") (pintype "passive"))
      (node (ref "BUFFER2") (pin "20") (pinfunction "20_20") (pintype "passive"))
      (node (ref "BUFFER3") (pin "20") (pinfunction "20_20") (pintype "passive"))
      (node (ref "C1") (pin "1") (pinfunction "1_1") (pintype "passive"))
      (node (ref "C10") (pin "1") (pinfunction "1_1") (pintype "passive"))
      (node (ref "C11") (pin "1") (pinfunction "1_1") (pintype "passive"))
      (node (ref "C12") (pin "1") (pinfunction "1_1") (pintype "passive"))
      (node (ref "C6") (pin "1") (pinfunction "1_1") (pintype "passive"))
      (node (ref "C8") (pin "1") (pinfunction "1_1") (pintype "passive"))
      (node (ref "CABLE1") (pin "12") (pinfunction "12_12") (pintype "passive"))
      (node (ref "CABLE10") (pin "12") (pinfunction "12_12") (pintype "passive"))
      (node (ref "CABLE2") (pin "12") (pinfunction "12_12") (pintype "passive"))
      (node (ref "CABLE3") (pin "12") (pinfunction "12_12") (pintype "passive"))
      (node (ref "CABLE4") (pin "12") (pinfunction "12_12") (pintype "passive"))
      (node (ref "CABLE5") (pin "12") (pinfunction "12_12") (pintype "passive"))
      (node (ref "CABLE6") (pin "12") (pinfunction "12_12") (pintype "passive"))
      (node (ref "CABLE7") (pin "12") (pinfunction "12_12") (pintype "passive"))
      (node (ref "CABLE8") (pin "12") (pinfunction "12_12") (pintype "passive"))
      (node (ref "CABLE9") (pin "12") (pinfunction "12_12") (pintype "passive"))
      (node (ref "DECADE1") (pin "16") (pinfunction "VCC_16") (pintype "power_in"))
      (node (ref "DECADE2") (pin "16") (pinfunction "VCC_16") (pintype "power_in"))
      (node (ref "IC1") (pin "8") (pinfunction "V+_8") (pintype "power_in"))
      (node (ref "JP1") (pin "1") (pinfunction "1_1") (pintype "passive"))
    )
    (net (code "57") (name "Net-(C1-Pad2)") (class "Default")
      (node (ref "C1") (pin "2") (pinfunction "2_2") (pintype "passive"))
      (node (ref "D3") (pin "C") (pinfunction "C_C") (pintype "passive"))
      (node (ref "K1") (pin "2") (pinfunction "2_2") (pintype "passive"))
    )
    (net (code "58") (name "Net-(POT1-PadE)") (class "Default")
      (node (ref "POT1") (pin "E") (pinfunction "E_E") (pintype "passive"))
      (node (ref "POT1") (pin "S") (pinfunction "S_S") (pintype "passive"))
      (node (ref "R3") (pin "1") (pinfunction "1_1") (pintype "passive"))
    )
    (net (code "59") (name "unconnected-(BUFFER1-Pad6)") (class "Default")
      (node (ref "BUFFER1") (pin "6") (pinfunction "6_6") (pintype "passive"))
    )
    (net (code "60") (name "unconnected-(BUFFER1-Pad7)") (class "Default")
      (node (ref "BUFFER1") (pin "7") (pinfunction "7_7") (pintype "passive"))
    )
    (net (code "61") (name "unconnected-(BUFFER1-Pad8)") (class "Default")
      (node (ref "BUFFER1") (pin "8") (pinfunction "8_8") (pintype "passive"))
    )
    (net (code "62") (name "unconnected-(BUFFER1-Pad9)") (class "Default")
      (node (ref "BUFFER1") (pin "9") (pinfunction "9_9") (pintype "passive"))
    )
    (net (code "63") (name "unconnected-(BUFFER1-Pad11)") (class "Default")
      (node (ref "BUFFER1") (pin "11") (pinfunction "11_11") (pintype "passive"))
    )
    (net (code "64") (name "unconnected-(BUFFER1-Pad12)") (class "Default")
      (node (ref "BUFFER1") (pin "12") (pinfunction "12_12") (pintype "passive"))
    )
    (net (code "65") (name "unconnected-(BUFFER1-Pad13)") (class "Default")
      (node (ref "BUFFER1") (pin "13") (pinfunction "13_13") (pintype "passive"))
    )
    (net (code "66") (name "unconnected-(BUFFER1-Pad14)") (class "Default")
      (node (ref "BUFFER1") (pin "14") (pinfunction "14_14") (pintype "passive"))
    )
    (net (code "67") (name "unconnected-(C3-Pad1)") (class "Default")
      (node (ref "C3") (pin "1") (pinfunction "1_1") (pintype "passive"))
    )
    (net (code "68") (name "unconnected-(DECADE2-2CKB-Pad12)") (class "Default")
      (node (ref "DECADE2") (pin "12") (pinfunction "2CKB_12") (pintype "input"))
    )
    (net (code "69") (name "unconnected-(K1-Pad8)") (class "Default")
      (node (ref "K1") (pin "8") (pinfunction "8_8") (pintype "passive"))
    )
    (net (code "70") (name "unconnected-(K1-Pad9)") (class "Default")
      (node (ref "K1") (pin "9") (pinfunction "9_9") (pintype "passive"))
    )
    (net (code "71") (name "unconnected-(K1-Pad13)") (class "Default")
      (node (ref "K1") (pin "13") (pinfunction "13_13") (pintype "passive"))
    )
    (net (code "72") (name "unconnected-(K1-Pad14)") (class "Default")
      (node (ref "K1") (pin "14") (pinfunction "14_14") (pintype "passive"))
    )
  )
)
